# rev1.net
KiCad netlist of a schematic drawn in EAGLE
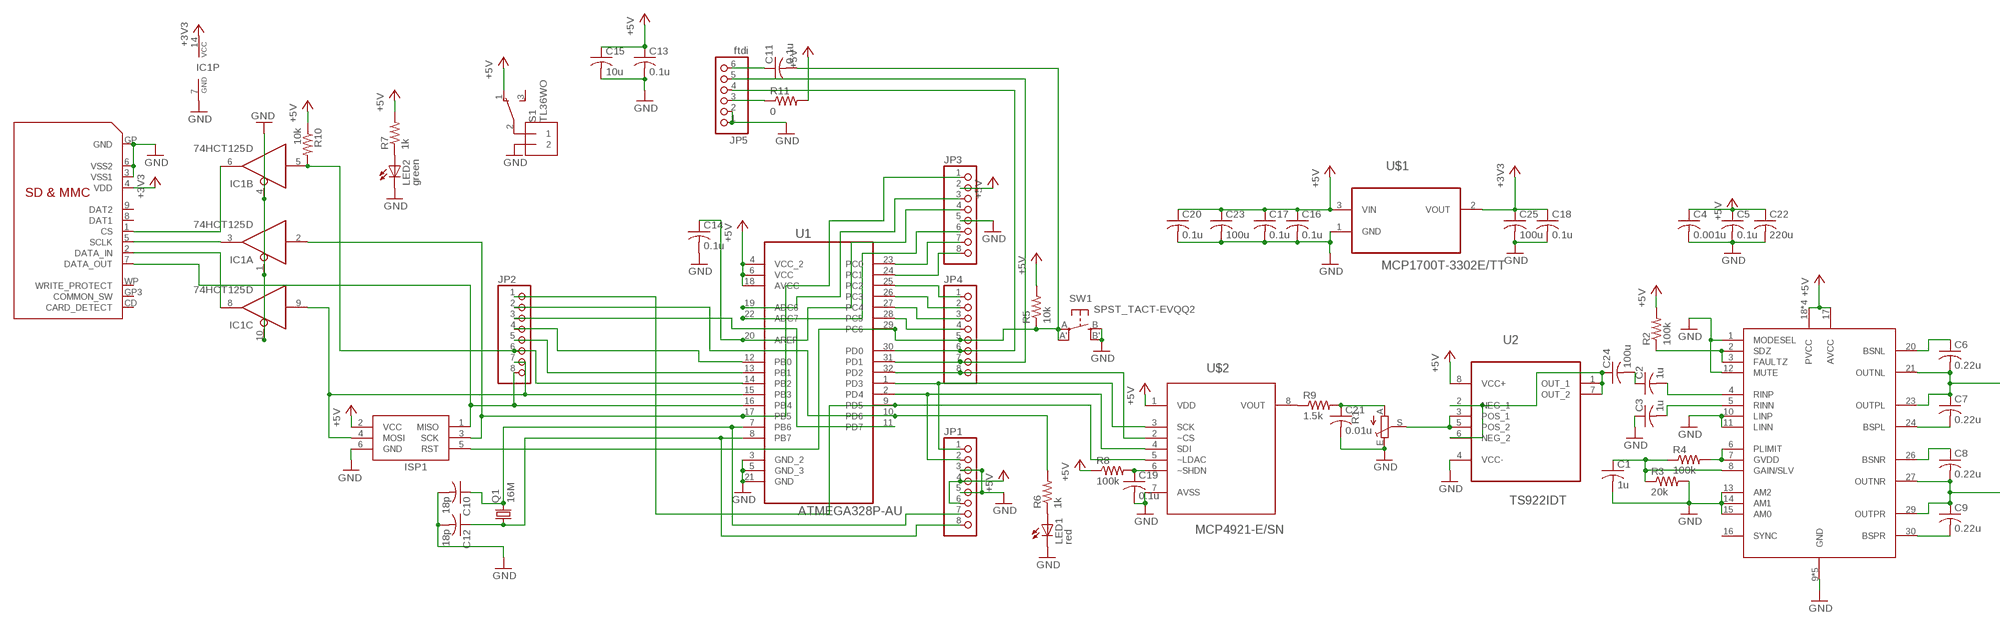
[diagram p0: schematic, sheet 1, part 1 of 2]
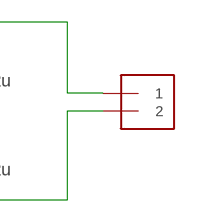
[diagram p1: schematic, sheet 1, part 2 of 2]

(export (version "E")
  (design (tool "Eeschema 10.0.6"))
  (components
    (comp (ref "C1")
      (value "1u")
      (footprint "eagle-import:C0603")
      (libsource (lib "eagle-import") (part "C-USC0603"))
    )
    (comp (ref "C2")
      (value "1u")
      (footprint "eagle-import:C0603")
      (libsource (lib "eagle-import") (part "C-USC0603"))
    )
    (comp (ref "C3")
      (value "1u")
      (footprint "eagle-import:C0603")
      (libsource (lib "eagle-import") (part "C-USC0603"))
    )
    (comp (ref "C4")
      (value "0.001u")
      (footprint "eagle-import:C0603")
      (libsource (lib "eagle-import") (part "C-USC0603"))
    )
    (comp (ref "C5")
      (value "0.1u")
      (footprint "eagle-import:C0603")
      (libsource (lib "eagle-import") (part "C-USC0603"))
    )
    (comp (ref "C6")
      (value "0.22u")
      (footprint "eagle-import:C0603")
      (libsource (lib "eagle-import") (part "C-USC0603"))
    )
    (comp (ref "C7")
      (value "0.22u")
      (footprint "eagle-import:C0603")
      (libsource (lib "eagle-import") (part "C-USC0603"))
    )
    (comp (ref "C8")
      (value "0.22u")
      (footprint "eagle-import:C0603")
      (libsource (lib "eagle-import") (part "C-USC0603"))
    )
    (comp (ref "C9")
      (value "0.22u")
      (footprint "eagle-import:C0603")
      (libsource (lib "eagle-import") (part "C-USC0603"))
    )
    (comp (ref "C10")
      (value "18p")
      (footprint "eagle-import:C0603")
      (libsource (lib "eagle-import") (part "C-USC0603"))
    )
    (comp (ref "C11")
      (value "0.1u")
      (footprint "eagle-import:C0603")
      (libsource (lib "eagle-import") (part "C-USC0603"))
    )
    (comp (ref "C12")
      (value "18p")
      (footprint "eagle-import:C0603")
      (libsource (lib "eagle-import") (part "C-USC0603"))
    )
    (comp (ref "C13")
      (value "0.1u")
      (footprint "eagle-import:C0603")
      (libsource (lib "eagle-import") (part "C-USC0603"))
    )
    (comp (ref "C14")
      (value "0.1u")
      (footprint "eagle-import:C0603")
      (libsource (lib "eagle-import") (part "C-USC0603"))
    )
    (comp (ref "C15")
      (value "10u")
      (footprint "eagle-import:C025-050X050")
      (libsource (lib "eagle-import") (part "C-US025-050X050"))
    )
    (comp (ref "C16")
      (value "0.1u")
      (footprint "eagle-import:C0603")
      (libsource (lib "eagle-import") (part "C-USC0603"))
    )
    (comp (ref "C17")
      (value "0.1u")
      (footprint "eagle-import:C0603")
      (libsource (lib "eagle-import") (part "C-USC0603"))
    )
    (comp (ref "C18")
      (value "0.1u")
      (footprint "eagle-import:C0603")
      (libsource (lib "eagle-import") (part "C-USC0603"))
    )
    (comp (ref "C19")
      (value "0.1u")
      (footprint "eagle-import:C0603")
      (libsource (lib "eagle-import") (part "C-USC0603"))
    )
    (comp (ref "C20")
      (value "0.1u")
      (footprint "eagle-import:C0603")
      (libsource (lib "eagle-import") (part "C-USC0603"))
    )
    (comp (ref "C21")
      (value "0.01u")
      (footprint "eagle-import:C0603")
      (libsource (lib "eagle-import") (part "C-USC0603"))
    )
    (comp (ref "C22")
      (value "220u")
      (footprint "eagle-import:C025-060X050")
      (libsource (lib "eagle-import") (part "C-US025-060X050"))
    )
    (comp (ref "C23")
      (value "100u")
      (footprint "eagle-import:C025-050X050")
      (libsource (lib "eagle-import") (part "C-US025-050X050"))
    )
    (comp (ref "C24")
      (value "100u")
      (footprint "eagle-import:C025-050X050")
      (libsource (lib "eagle-import") (part "C-US025-050X050"))
    )
    (comp (ref "C25")
      (value "100u")
      (footprint "eagle-import:C025-050X050")
      (libsource (lib "eagle-import") (part "C-US025-050X050"))
    )
    (comp (ref "IC1")
      (value "74HCT125D")
      (footprint "eagle-import:SO14")
      (libsource (lib "eagle-import") (part "74125DHCT"))
    )
    (comp (ref "ISP1")
      (value "AVRISP-6")
      (footprint "eagle-import:AVRISP")
      (libsource (lib "eagle-import") (part "AVRISP-6"))
    )
    (comp (ref "J1")
      (value "POWER")
      (footprint "eagle-import:1X2-3.5MM")
      (libsource (lib "eagle-import") (part "1X2-3.5MM"))
    )
    (comp (ref "J2")
      (value "Speaker")
      (footprint "eagle-import:1X2-3.5MM")
      (libsource (lib "eagle-import") (part "1X2-3.5MM"))
    )
    (comp (ref "JP1")
      (value "PINHD-1X8BIG")
      (footprint "eagle-import:1X08-BIG")
      (libsource (lib "eagle-import") (part "PINHD-1X8BIG"))
    )
    (comp (ref "JP2")
      (value "PINHD-1X8BIG")
      (footprint "eagle-import:1X08-BIG")
      (libsource (lib "eagle-import") (part "PINHD-1X8BIG"))
    )
    (comp (ref "JP3")
      (value "PINHD-1X8BIG")
      (footprint "eagle-import:1X08-BIG")
      (libsource (lib "eagle-import") (part "PINHD-1X8BIG"))
    )
    (comp (ref "JP4")
      (value "PINHD-1X8BIG")
      (footprint "eagle-import:1X08-BIG")
      (libsource (lib "eagle-import") (part "PINHD-1X8BIG"))
    )
    (comp (ref "JP5")
      (value "ftdi")
      (footprint "eagle-import:1X06")
      (libsource (lib "eagle-import") (part "PINHD-1X6"))
    )
    (comp (ref "LED1")
      (value "red")
      (footprint "eagle-import:LED3MM")
      (libsource (lib "eagle-import") (part "LED3MM"))
    )
    (comp (ref "LED2")
      (value "green")
      (footprint "eagle-import:LED3MM")
      (libsource (lib "eagle-import") (part "LED3MM"))
    )
    (comp (ref "Q1")
      (value "16M")
      (footprint "eagle-import:HC49UP")
      (libsource (lib "eagle-import") (part "CRYSTALHC49UP"))
    )
    (comp (ref "R1")
      (value "TRIM_EU-CA9V")
      (footprint "eagle-import:CA9V")
      (libsource (lib "eagle-import") (part "TRIM_EU-CA9V"))
    )
    (comp (ref "R2")
      (value "100k")
      (footprint "eagle-import:R0603")
      (libsource (lib "eagle-import") (part "R-US_R0603"))
    )
    (comp (ref "R3")
      (value "20k")
      (footprint "eagle-import:R0603")
      (libsource (lib "eagle-import") (part "R-US_R0603"))
    )
    (comp (ref "R4")
      (value "100k")
      (footprint "eagle-import:R0603")
      (libsource (lib "eagle-import") (part "R-US_R0603"))
    )
    (comp (ref "R5")
      (value "10k")
      (footprint "eagle-import:R0603")
      (libsource (lib "eagle-import") (part "R-US_R0603"))
    )
    (comp (ref "R6")
      (value "1k")
      (footprint "eagle-import:R0603")
      (libsource (lib "eagle-import") (part "R-US_R0603"))
    )
    (comp (ref "R7")
      (value "1k")
      (footprint "eagle-import:R0603")
      (libsource (lib "eagle-import") (part "R-US_R0603"))
    )
    (comp (ref "R8")
      (value "100k")
      (footprint "eagle-import:R0603")
      (libsource (lib "eagle-import") (part "R-US_R0603"))
    )
    (comp (ref "R9")
      (value "1.5k")
      (footprint "eagle-import:R0603")
      (libsource (lib "eagle-import") (part "R-US_R0603"))
    )
    (comp (ref "R10")
      (value "10k")
      (footprint "eagle-import:R0603")
      (libsource (lib "eagle-import") (part "R-US_R0603"))
    )
    (comp (ref "R11")
      (value "0")
      (footprint "eagle-import:R0603")
      (libsource (lib "eagle-import") (part "R-US_R0603"))
    )
    (comp (ref "S1")
      (value "TL36WO")
      (footprint "eagle-import:TL3XWO")
      (libsource (lib "eagle-import") (part "TL36WO"))
    )
    (comp (ref "SW1")
      (value "SPST_TACT-EVQQ2")
      (footprint "eagle-import:EVQ-Q2")
      (libsource (lib "eagle-import") (part "SPST_TACT-EVQQ2"))
    )
    (comp (ref "U$1")
      (value "MCP1700T-3302E/TT")
      (footprint "eagle-import:SOT95P237X112-3N")
      (libsource (lib "eagle-import") (part "MCP1700T-3302E/TT"))
    )
    (comp (ref "U$2")
      (value "MCP4921-E/SN")
      (footprint "eagle-import:SOIC8-N_MC")
      (libsource (lib "eagle-import") (part "MCP4921-E/SN"))
    )
    (comp (ref "U$3")
      (value "SDMMC06132")
      (footprint "eagle-import:06132")
      (libsource (lib "eagle-import") (part "SDMMC06132"))
    )
    (comp (ref "U$4")
      (value "TPA3118D2DAP")
      (footprint "eagle-import:TPA3118D2DAP")
      (libsource (lib "eagle-import") (part "TPA3118D2DAP"))
    )
    (comp (ref "U1")
      (value "ATMEGA328P-AU")
      (footprint "eagle-import:QFP80P900X900X120-32N")
      (libsource (lib "eagle-import") (part "ATMEGA328P-AU"))
    )
    (comp (ref "U2")
      (value "TS922IDT")
      (footprint "eagle-import:SOIC127P600X175-8N")
      (libsource (lib "eagle-import") (part "TS922IDT"))
    )
  )
  (nets
    (net (code "1") (name "+3V3") (class "Default")
      (node (ref "C18") (pin "1") (pinfunction "1_1") (pintype "passive"))
      (node (ref "C25") (pin "1") (pinfunction "1_1") (pintype "passive"))
      (node (ref "IC1") (pin "14") (pinfunction "VCC_14") (pintype "power_in"))
      (node (ref "U$1") (pin "2") (pinfunction "VOUT_2") (pintype "output"))
      (node (ref "U$3") (pin "4") (pinfunction "VDD_4") (pintype "power_in"))
    )
    (net (code "2") (name "+5V") (class "Default")
      (node (ref "C13") (pin "1") (pinfunction "1_1") (pintype "passive"))
      (node (ref "C15") (pin "1") (pinfunction "1_1") (pintype "passive"))
      (node (ref "C16") (pin "1") (pinfunction "1_1") (pintype "passive"))
      (node (ref "C17") (pin "1") (pinfunction "1_1") (pintype "passive"))
      (node (ref "C20") (pin "1") (pinfunction "1_1") (pintype "passive"))
      (node (ref "C22") (pin "1") (pinfunction "1_1") (pintype "passive"))
      (node (ref "C23") (pin "1") (pinfunction "1_1") (pintype "passive"))
      (node (ref "C4") (pin "1") (pinfunction "1_1") (pintype "passive"))
      (node (ref "C5") (pin "1") (pinfunction "1_1") (pintype "passive"))
      (node (ref "ISP1") (pin "2") (pinfunction "VCC_2") (pintype "power_in"))
      (node (ref "JP1") (pin "4") (pinfunction "4_4") (pintype "passive"))
      (node (ref "JP1") (pin "6") (pinfunction "6_6") (pintype "passive"))
      (node (ref "JP3") (pin "2") (pinfunction "2_2") (pintype "passive"))
      (node (ref "R10") (pin "1") (pinfunction "1_1") (pintype "passive"))
      (node (ref "R11") (pin "2") (pinfunction "2_2") (pintype "passive"))
      (node (ref "R2") (pin "2") (pinfunction "2_2") (pintype "passive"))
      (node (ref "R5") (pin "2") (pinfunction "2_2") (pintype "passive"))
      (node (ref "R7") (pin "2") (pinfunction "2_2") (pintype "passive"))
      (node (ref "R8") (pin "1") (pinfunction "1_1") (pintype "passive"))
      (node (ref "S1") (pin "1") (pinfunction "O_1") (pintype "passive"))
      (node (ref "U$1") (pin "3") (pinfunction "VIN_3") (pintype "input"))
      (node (ref "U$2") (pin "1") (pinfunction "VDD_1") (pintype "power_in"))
      (node (ref "U$4") (pin "17") (pinfunction "AVCC_17") (pintype "bidirectional"))
      (node (ref "U$4") (pin "18") (pinfunction "PVCC_18") (pintype "bidirectional"))
      (node (ref "U$4") (pin "19") (pinfunction "PVCC_19") (pintype "bidirectional"))
      (node (ref "U$4") (pin "31") (pinfunction "PVCC_31") (pintype "bidirectional"))
      (node (ref "U$4") (pin "32") (pinfunction "PVCC_32") (pintype "bidirectional"))
      (node (ref "U1") (pin "18") (pinfunction "AVCC_18") (pintype "power_in"))
      (node (ref "U1") (pin "4") (pinfunction "VCC_2_4") (pintype "power_in"))
      (node (ref "U1") (pin "6") (pinfunction "VCC_6") (pintype "power_in"))
      (node (ref "U2") (pin "8") (pinfunction "VCC+_8") (pintype "power_in"))
    )
    (net (code "3") (name "GND") (class "Default")
      (node (ref "C1") (pin "2") (pinfunction "2_2") (pintype "passive"))
      (node (ref "C10") (pin "2") (pinfunction "2_2") (pintype "passive"))
      (node (ref "C12") (pin "2") (pinfunction "2_2") (pintype "passive"))
      (node (ref "C13") (pin "2") (pinfunction "2_2") (pintype "passive"))
      (node (ref "C14") (pin "2") (pinfunction "2_2") (pintype "passive"))
      (node (ref "C15") (pin "2") (pinfunction "2_2") (pintype "passive"))
      (node (ref "C16") (pin "2") (pinfunction "2_2") (pintype "passive"))
      (node (ref "C17") (pin "2") (pinfunction "2_2") (pintype "passive"))
      (node (ref "C18") (pin "2") (pinfunction "2_2") (pintype "passive"))
      (node (ref "C19") (pin "2") (pinfunction "2_2") (pintype "passive"))
      (node (ref "C20") (pin "2") (pinfunction "2_2") (pintype "passive"))
      (node (ref "C21") (pin "2") (pinfunction "2_2") (pintype "passive"))
      (node (ref "C22") (pin "2") (pinfunction "2_2") (pintype "passive"))
      (node (ref "C23") (pin "2") (pinfunction "2_2") (pintype "passive"))
      (node (ref "C25") (pin "2") (pinfunction "2_2") (pintype "passive"))
      (node (ref "C3") (pin "1") (pinfunction "1_1") (pintype "passive"))
      (node (ref "C4") (pin "2") (pinfunction "2_2") (pintype "passive"))
      (node (ref "C5") (pin "2") (pinfunction "2_2") (pintype "passive"))
      (node (ref "IC1") (pin "1") (pinfunction "OE_1") (pintype "input"))
      (node (ref "IC1") (pin "10") (pinfunction "OE_10") (pintype "input"))
      (node (ref "IC1") (pin "4") (pinfunction "OE_4") (pintype "input"))
      (node (ref "IC1") (pin "7") (pinfunction "GND_7") (pintype "power_in"))
      (node (ref "ISP1") (pin "6") (pinfunction "GND_6") (pintype "power_in"))
      (node (ref "J1") (pin "2") (pinfunction "2_2") (pintype "passive"))
      (node (ref "JP1") (pin "3") (pinfunction "3_3") (pintype "passive"))
      (node (ref "JP1") (pin "5") (pinfunction "5_5") (pintype "passive"))
      (node (ref "JP3") (pin "5") (pinfunction "5_5") (pintype "passive"))
      (node (ref "JP5") (pin "1") (pinfunction "1_1") (pintype "passive"))
      (node (ref "JP5") (pin "2") (pinfunction "2_2") (pintype "passive"))
      (node (ref "LED1") (pin "K") (pinfunction "C_K") (pintype "passive"))
      (node (ref "LED2") (pin "K") (pinfunction "C_K") (pintype "passive"))
      (node (ref "R1") (pin "E") (pinfunction "E_E") (pintype "passive"))
      (node (ref "R3") (pin "2") (pinfunction "2_2") (pintype "passive"))
      (node (ref "SW1") (pin "B") (pinfunction "S_B") (pintype "passive"))
      (node (ref "SW1") (pin "B'") (pinfunction "S1_B'") (pintype "passive"))
      (node (ref "U$1") (pin "1") (pinfunction "GND_1") (pintype "passive"))
      (node (ref "U$2") (pin "7") (pinfunction "AVSS_7") (pintype "power_in"))
      (node (ref "U$3") (pin "3") (pinfunction "VSS1_3") (pintype "power_in"))
      (node (ref "U$3") (pin "6") (pinfunction "VSS2_6") (pintype "power_in"))
      (node (ref "U$3") (pin "GP") (pinfunction "GND_GP") (pintype "power_in"))
      (node (ref "U$4") (pin "1") (pinfunction "MODESEL_1") (pintype "bidirectional"))
      (node (ref "U$4") (pin "10") (pinfunction "LINP_10") (pintype "bidirectional"))
      (node (ref "U$4") (pin "11") (pinfunction "LINN_11") (pintype "bidirectional"))
      (node (ref "U$4") (pin "12") (pinfunction "MUTE_12") (pintype "bidirectional"))
      (node (ref "U$4") (pin "13") (pinfunction "AM2_13") (pintype "bidirectional"))
      (node (ref "U$4") (pin "14") (pinfunction "AM1_14") (pintype "bidirectional"))
      (node (ref "U$4") (pin "15") (pinfunction "AM0_15") (pintype "bidirectional"))
      (node (ref "U$4") (pin "22") (pinfunction "GND_22") (pintype "bidirectional"))
      (node (ref "U$4") (pin "25") (pinfunction "GND_25") (pintype "bidirectional"))
      (node (ref "U$4") (pin "28") (pinfunction "GND_28") (pintype "bidirectional"))
      (node (ref "U$4") (pin "33") (pinfunction "GND_33") (pintype "bidirectional"))
      (node (ref "U$4") (pin "9") (pinfunction "GND_9") (pintype "bidirectional"))
      (node (ref "U1") (pin "21") (pinfunction "GND_21") (pintype "passive"))
      (node (ref "U1") (pin "3") (pinfunction "GND_2_3") (pintype "passive"))
      (node (ref "U1") (pin "5") (pinfunction "GND_3_5") (pintype "passive"))
      (node (ref "U2") (pin "4") (pinfunction "VCC-_4") (pintype "power_in"))
    )
    (net (code "4") (name "Net-(C2-Pad1)") (class "Default")
      (node (ref "C2") (pin "1") (pinfunction "1_1") (pintype "passive"))
      (node (ref "C24") (pin "2") (pinfunction "2_2") (pintype "passive"))
    )
    (net (code "5") (name "Net-(C11-Pad1)") (class "Default")
      (node (ref "C11") (pin "1") (pinfunction "1_1") (pintype "passive"))
      (node (ref "JP5") (pin "6") (pinfunction "6_6") (pintype "passive"))
    )
    (net (code "6") (name "Net-(C21-Pad1)") (class "Default")
      (node (ref "C21") (pin "1") (pinfunction "1_1") (pintype "passive"))
      (node (ref "R1") (pin "A") (pinfunction "A_A") (pintype "passive"))
      (node (ref "R9") (pin "2") (pinfunction "2_2") (pintype "passive"))
    )
    (net (code "7") (name "Net-(IC1A-I)") (class "Default")
      (node (ref "IC1") (pin "2") (pinfunction "I_2") (pintype "input"))
      (node (ref "ISP1") (pin "3") (pinfunction "SCK_3") (pintype "output"))
      (node (ref "JP3") (pin "1") (pinfunction "1_1") (pintype "passive"))
      (node (ref "U1") (pin "17") (pinfunction "PB5_17") (pintype "bidirectional"))
    )
    (net (code "8") (name "Net-(IC1A-O)") (class "Default")
      (node (ref "IC1") (pin "3") (pinfunction "O_3") (pintype "tri_state"))
      (node (ref "U$3") (pin "5") (pinfunction "SCLK_5") (pintype "input"))
    )
    (net (code "9") (name "Net-(IC1B-I)") (class "Default")
      (node (ref "IC1") (pin "5") (pinfunction "I_5") (pintype "input"))
      (node (ref "JP2") (pin "6") (pinfunction "6_6") (pintype "passive"))
      (node (ref "R10") (pin "2") (pinfunction "2_2") (pintype "passive"))
      (node (ref "U1") (pin "14") (pinfunction "PB2_14") (pintype "bidirectional"))
    )
    (net (code "10") (name "Net-(IC1B-O)") (class "Default")
      (node (ref "IC1") (pin "6") (pinfunction "O_6") (pintype "tri_state"))
      (node (ref "U$3") (pin "1") (pinfunction "CS_1") (pintype "input"))
    )
    (net (code "11") (name "Net-(IC1C-I)") (class "Default")
      (node (ref "IC1") (pin "9") (pinfunction "I_9") (pintype "input"))
      (node (ref "ISP1") (pin "4") (pinfunction "MOSI_4") (pintype "output"))
      (node (ref "JP2") (pin "7") (pinfunction "7_7") (pintype "passive"))
      (node (ref "U1") (pin "15") (pinfunction "PB3_15") (pintype "bidirectional"))
    )
    (net (code "12") (name "Net-(IC1C-O)") (class "Default")
      (node (ref "IC1") (pin "8") (pinfunction "O_8") (pintype "tri_state"))
      (node (ref "U$3") (pin "2") (pinfunction "DATA_IN_2") (pintype "input"))
    )
    (net (code "13") (name "Net-(ISP1-MISO)") (class "Default")
      (node (ref "ISP1") (pin "1") (pinfunction "MISO_1") (pintype "input"))
      (node (ref "JP2") (pin "8") (pinfunction "8_8") (pintype "passive"))
      (node (ref "U$3") (pin "7") (pinfunction "DATA_OUT_7") (pintype "output"))
      (node (ref "U1") (pin "16") (pinfunction "PB4_16") (pintype "bidirectional"))
    )
    (net (code "14") (name "Net-(ISP1-RST)") (class "Default")
      (node (ref "C11") (pin "2") (pinfunction "2_2") (pintype "passive"))
      (node (ref "ISP1") (pin "5") (pinfunction "RST_5") (pintype "output"))
      (node (ref "JP4") (pin "5") (pinfunction "5_5") (pintype "passive"))
      (node (ref "R5") (pin "1") (pinfunction "1_1") (pintype "passive"))
      (node (ref "SW1") (pin "A") (pinfunction "P_A") (pintype "passive"))
      (node (ref "SW1") (pin "A'") (pinfunction "P1_A'") (pintype "passive"))
      (node (ref "U1") (pin "29") (pinfunction "PC6_29") (pintype "bidirectional"))
    )
    (net (code "15") (name "Net-(JP5-Pad3)") (class "Default")
      (node (ref "JP5") (pin "3") (pinfunction "3_3") (pintype "passive"))
      (node (ref "R11") (pin "1") (pinfunction "1_1") (pintype "passive"))
    )
    (net (code "16") (name "Net-(LED1-PadA)") (class "Default")
      (node (ref "LED1") (pin "A") (pinfunction "A_A") (pintype "passive"))
      (node (ref "R6") (pin "1") (pinfunction "1_1") (pintype "passive"))
    )
    (net (code "17") (name "Net-(LED2-PadA)") (class "Default")
      (node (ref "LED2") (pin "A") (pinfunction "A_A") (pintype "passive"))
      (node (ref "R7") (pin "1") (pinfunction "1_1") (pintype "passive"))
    )
    (net (code "18") (name "Net-(S1-P)") (class "Default")
      (node (ref "J1") (pin "1") (pinfunction "1_1") (pintype "passive"))
      (node (ref "S1") (pin "2") (pinfunction "P_2") (pintype "passive"))
    )
    (net (code "19") (name "Net-(U$2-SCK)") (class "Default")
      (node (ref "JP1") (pin "1") (pinfunction "1_1") (pintype "passive"))
      (node (ref "U$2") (pin "3") (pinfunction "SCK_3") (pintype "input"))
      (node (ref "U1") (pin "1") (pinfunction "PD3_1") (pintype "bidirectional"))
    )
    (net (code "20") (name "Net-(U$2-SDI)") (class "Default")
      (node (ref "JP1") (pin "2") (pinfunction "2_2") (pintype "passive"))
      (node (ref "U$2") (pin "4") (pinfunction "SDI_4") (pintype "input"))
      (node (ref "U1") (pin "2") (pinfunction "PD4_2") (pintype "bidirectional"))
    )
    (net (code "21") (name "Net-(U$2-VOUT)") (class "Default")
      (node (ref "R9") (pin "1") (pinfunction "1_1") (pintype "passive"))
      (node (ref "U$2") (pin "8") (pinfunction "VOUT_8") (pintype "output"))
    )
    (net (code "22") (name "Net-(U$2-~{CS})") (class "Default")
      (node (ref "JP4") (pin "8") (pinfunction "8_8") (pintype "passive"))
      (node (ref "U$2") (pin "2") (pinfunction "~{CS}_2") (pintype "input"))
      (node (ref "U1") (pin "32") (pinfunction "PD2_32") (pintype "bidirectional"))
    )
    (net (code "23") (name "Net-(U$2-~{LDAC})") (class "Default")
      (node (ref "JP2") (pin "1") (pinfunction "1_1") (pintype "passive"))
      (node (ref "U$2") (pin "5") (pinfunction "~{LDAC}_5") (pintype "input"))
      (node (ref "U1") (pin "9") (pinfunction "PD5_9") (pintype "bidirectional"))
    )
    (net (code "24") (name "Net-(U$2-~{SHDN})") (class "Default")
      (node (ref "C19") (pin "1") (pinfunction "1_1") (pintype "passive"))
      (node (ref "R8") (pin "2") (pinfunction "2_2") (pintype "passive"))
      (node (ref "U$2") (pin "6") (pinfunction "~{SHDN}_6") (pintype "input"))
    )
    (net (code "25") (name "Net-(U$4-BSNL)") (class "Default")
      (node (ref "C6") (pin "1") (pinfunction "1_1") (pintype "passive"))
      (node (ref "U$4") (pin "20") (pinfunction "BSNL_20") (pintype "bidirectional"))
    )
    (net (code "26") (name "Net-(U$4-BSNR)") (class "Default")
      (node (ref "C8") (pin "1") (pinfunction "1_1") (pintype "passive"))
      (node (ref "U$4") (pin "26") (pinfunction "BSNR_26") (pintype "bidirectional"))
    )
    (net (code "27") (name "Net-(U$4-BSPL)") (class "Default")
      (node (ref "C7") (pin "2") (pinfunction "2_2") (pintype "passive"))
      (node (ref "U$4") (pin "24") (pinfunction "BSPL_24") (pintype "bidirectional"))
    )
    (net (code "28") (name "Net-(U$4-BSPR)") (class "Default")
      (node (ref "C9") (pin "2") (pinfunction "2_2") (pintype "passive"))
      (node (ref "U$4") (pin "30") (pinfunction "BSPR_30") (pintype "bidirectional"))
    )
    (net (code "29") (name "Net-(U$4-FAULTZ)") (class "Default")
      (node (ref "R2") (pin "1") (pinfunction "1_1") (pintype "passive"))
      (node (ref "U$4") (pin "2") (pinfunction "SDZ_2") (pintype "bidirectional"))
      (node (ref "U$4") (pin "3") (pinfunction "FAULTZ_3") (pintype "bidirectional"))
    )
    (net (code "30") (name "Net-(U$4-GAIN{slash}SLV)") (class "Default")
      (node (ref "C1") (pin "1") (pinfunction "1_1") (pintype "passive"))
      (node (ref "R3") (pin "1") (pinfunction "1_1") (pintype "passive"))
      (node (ref "R4") (pin "1") (pinfunction "1_1") (pintype "passive"))
      (node (ref "U$4") (pin "8") (pinfunction "GAIN/SLV_8") (pintype "bidirectional"))
    )
    (net (code "31") (name "Net-(U$4-GVDD)") (class "Default")
      (node (ref "R4") (pin "2") (pinfunction "2_2") (pintype "passive"))
      (node (ref "U$4") (pin "6") (pinfunction "PLIMIT_6") (pintype "bidirectional"))
      (node (ref "U$4") (pin "7") (pinfunction "GVDD_7") (pintype "bidirectional"))
    )
    (net (code "32") (name "Net-(U$4-OUTNL)") (class "Default")
      (node (ref "C6") (pin "2") (pinfunction "2_2") (pintype "passive"))
      (node (ref "C7") (pin "1") (pinfunction "1_1") (pintype "passive"))
      (node (ref "J2") (pin "1") (pinfunction "1_1") (pintype "passive"))
      (node (ref "U$4") (pin "21") (pinfunction "OUTNL_21") (pintype "bidirectional"))
      (node (ref "U$4") (pin "23") (pinfunction "OUTPL_23") (pintype "bidirectional"))
    )
    (net (code "33") (name "Net-(U$4-OUTNR)") (class "Default")
      (node (ref "C8") (pin "2") (pinfunction "2_2") (pintype "passive"))
      (node (ref "C9") (pin "1") (pinfunction "1_1") (pintype "passive"))
      (node (ref "J2") (pin "2") (pinfunction "2_2") (pintype "passive"))
      (node (ref "U$4") (pin "27") (pinfunction "OUTNR_27") (pintype "bidirectional"))
      (node (ref "U$4") (pin "29") (pinfunction "OUTPR_29") (pintype "bidirectional"))
    )
    (net (code "34") (name "Net-(U$4-RINN)") (class "Default")
      (node (ref "C3") (pin "2") (pinfunction "2_2") (pintype "passive"))
      (node (ref "U$4") (pin "5") (pinfunction "RINN_5") (pintype "bidirectional"))
    )
    (net (code "35") (name "Net-(U$4-RINP)") (class "Default")
      (node (ref "C2") (pin "2") (pinfunction "2_2") (pintype "passive"))
      (node (ref "U$4") (pin "4") (pinfunction "RINP_4") (pintype "bidirectional"))
    )
    (net (code "36") (name "Net-(U1-ADC6)") (class "Default")
      (node (ref "JP3") (pin "3") (pinfunction "3_3") (pintype "passive"))
      (node (ref "U1") (pin "19") (pinfunction "ADC6_19") (pintype "input"))
    )
    (net (code "37") (name "Net-(U1-ADC7)") (class "Default")
      (node (ref "JP3") (pin "6") (pinfunction "6_6") (pintype "passive"))
      (node (ref "U1") (pin "22") (pinfunction "ADC7_22") (pintype "input"))
    )
    (net (code "38") (name "Net-(U1-AREF)") (class "Default")
      (node (ref "C14") (pin "1") (pinfunction "1_1") (pintype "passive"))
      (node (ref "JP3") (pin "4") (pinfunction "4_4") (pintype "passive"))
      (node (ref "U1") (pin "20") (pinfunction "AREF_20") (pintype "input"))
    )
    (net (code "39") (name "Net-(U1-PB0)") (class "Default")
      (node (ref "JP2") (pin "4") (pinfunction "4_4") (pintype "passive"))
      (node (ref "U1") (pin "12") (pinfunction "PB0_12") (pintype "bidirectional"))
    )
    (net (code "40") (name "Net-(U1-PB1)") (class "Default")
      (node (ref "JP2") (pin "5") (pinfunction "5_5") (pintype "passive"))
      (node (ref "U1") (pin "13") (pinfunction "PB1_13") (pintype "bidirectional"))
    )
    (net (code "41") (name "Net-(U1-PB6)") (class "Default")
      (node (ref "C10") (pin "1") (pinfunction "1_1") (pintype "passive"))
      (node (ref "JP1") (pin "7") (pinfunction "7_7") (pintype "passive"))
      (node (ref "Q1") (pin "2") (pinfunction "2_2") (pintype "passive"))
      (node (ref "U1") (pin "7") (pinfunction "PB6_7") (pintype "bidirectional"))
    )
    (net (code "42") (name "Net-(U1-PB7)") (class "Default")
      (node (ref "C12") (pin "1") (pinfunction "1_1") (pintype "passive"))
      (node (ref "JP1") (pin "8") (pinfunction "8_8") (pintype "passive"))
      (node (ref "Q1") (pin "1") (pinfunction "1_1") (pintype "passive"))
      (node (ref "U1") (pin "8") (pinfunction "PB7_8") (pintype "bidirectional"))
    )
    (net (code "43") (name "Net-(U1-PC0)") (class "Default")
      (node (ref "JP3") (pin "7") (pinfunction "7_7") (pintype "passive"))
      (node (ref "U1") (pin "23") (pinfunction "PC0_23") (pintype "bidirectional"))
    )
    (net (code "44") (name "Net-(U1-PC1)") (class "Default")
      (node (ref "JP3") (pin "8") (pinfunction "8_8") (pintype "passive"))
      (node (ref "U1") (pin "24") (pinfunction "PC1_24") (pintype "bidirectional"))
    )
    (net (code "45") (name "Net-(U1-PC2)") (class "Default")
      (node (ref "JP4") (pin "1") (pinfunction "1_1") (pintype "passive"))
      (node (ref "U1") (pin "25") (pinfunction "PC2_25") (pintype "bidirectional"))
    )
    (net (code "46") (name "Net-(U1-PC3)") (class "Default")
      (node (ref "JP4") (pin "2") (pinfunction "2_2") (pintype "passive"))
      (node (ref "U1") (pin "26") (pinfunction "PC3_26") (pintype "bidirectional"))
    )
    (net (code "47") (name "Net-(U1-PC4)") (class "Default")
      (node (ref "JP4") (pin "3") (pinfunction "3_3") (pintype "passive"))
      (node (ref "U1") (pin "27") (pinfunction "PC4_27") (pintype "bidirectional"))
    )
    (net (code "48") (name "Net-(U1-PC5)") (class "Default")
      (node (ref "JP4") (pin "4") (pinfunction "4_4") (pintype "passive"))
      (node (ref "U1") (pin "28") (pinfunction "PC5_28") (pintype "bidirectional"))
    )
    (net (code "49") (name "Net-(U1-PD0)") (class "Default")
      (node (ref "JP4") (pin "6") (pinfunction "6_6") (pintype "passive"))
      (node (ref "JP5") (pin "4") (pinfunction "4_4") (pintype "passive"))
      (node (ref "U1") (pin "30") (pinfunction "PD0_30") (pintype "bidirectional"))
    )
    (net (code "50") (name "Net-(U1-PD1)") (class "Default")
      (node (ref "JP4") (pin "7") (pinfunction "7_7") (pintype "passive"))
      (node (ref "JP5") (pin "5") (pinfunction "5_5") (pintype "passive"))
      (node (ref "U1") (pin "31") (pinfunction "PD1_31") (pintype "bidirectional"))
    )
    (net (code "51") (name "Net-(U1-PD6)") (class "Default")
      (node (ref "JP2") (pin "2") (pinfunction "2_2") (pintype "passive"))
      (node (ref "R6") (pin "2") (pinfunction "2_2") (pintype "passive"))
      (node (ref "U1") (pin "10") (pinfunction "PD6_10") (pintype "bidirectional"))
    )
    (net (code "52") (name "Net-(U1-PD7)") (class "Default")
      (node (ref "JP2") (pin "3") (pinfunction "3_3") (pintype "passive"))
      (node (ref "U1") (pin "11") (pinfunction "PD7_11") (pintype "bidirectional"))
    )
    (net (code "53") (name "Net-(U2-NEG_1)") (class "Default")
      (node (ref "C24") (pin "1") (pinfunction "1_1") (pintype "passive"))
      (node (ref "U2") (pin "1") (pinfunction "OUT_1_1") (pintype "output"))
      (node (ref "U2") (pin "2") (pinfunction "NEG_1_2") (pintype "input"))
      (node (ref "U2") (pin "6") (pinfunction "NEG_2_6") (pintype "input"))
      (node (ref "U2") (pin "7") (pinfunction "OUT_2_7") (pintype "output"))
    )
    (net (code "54") (name "Net-(U2-POS_1)") (class "Default")
      (node (ref "R1") (pin "S") (pinfunction "S_S") (pintype "passive"))
      (node (ref "U2") (pin "3") (pinfunction "POS_1_3") (pintype "input"))
      (node (ref "U2") (pin "5") (pinfunction "POS_2_5") (pintype "input"))
    )
    (net (code "55") (name "unconnected-(S1-S-Pad3)") (class "Default")
      (node (ref "S1") (pin "3") (pinfunction "S_3") (pintype "passive"))
    )
    (net (code "56") (name "unconnected-(U$3-CARD_DETECT-PadCD)") (class "Default")
      (node (ref "U$3") (pin "CD") (pinfunction "CARD_DETECT_CD") (pintype "passive"))
    )
    (net (code "57") (name "unconnected-(U$3-COMMON_SW-PadGP3)") (class "Default")
      (node (ref "U$3") (pin "GP3") (pinfunction "COMMON_SW_GP3") (pintype "passive"))
    )
    (net (code "58") (name "unconnected-(U$3-DAT1-Pad8)") (class "Default")
      (node (ref "U$3") (pin "8") (pinfunction "DAT1_8") (pintype "bidirectional"))
    )
    (net (code "59") (name "unconnected-(U$3-DAT2-Pad9)") (class "Default")
      (node (ref "U$3") (pin "9") (pinfunction "DAT2_9") (pintype "bidirectional"))
    )
    (net (code "60") (name "unconnected-(U$3-WRITE_PROTECT-PadWP)") (class "Default")
      (node (ref "U$3") (pin "WP") (pinfunction "WRITE_PROTECT_WP") (pintype "passive"))
    )
    (net (code "61") (name "unconnected-(U$4-SYNC-Pad16)") (class "Default")
      (node (ref "U$4") (pin "16") (pinfunction "SYNC_16") (pintype "bidirectional"))
    )
  )
)
